# Old_Shutters_Signal_Interface.net
KiCad netlist of a schematic drawn in EAGLE
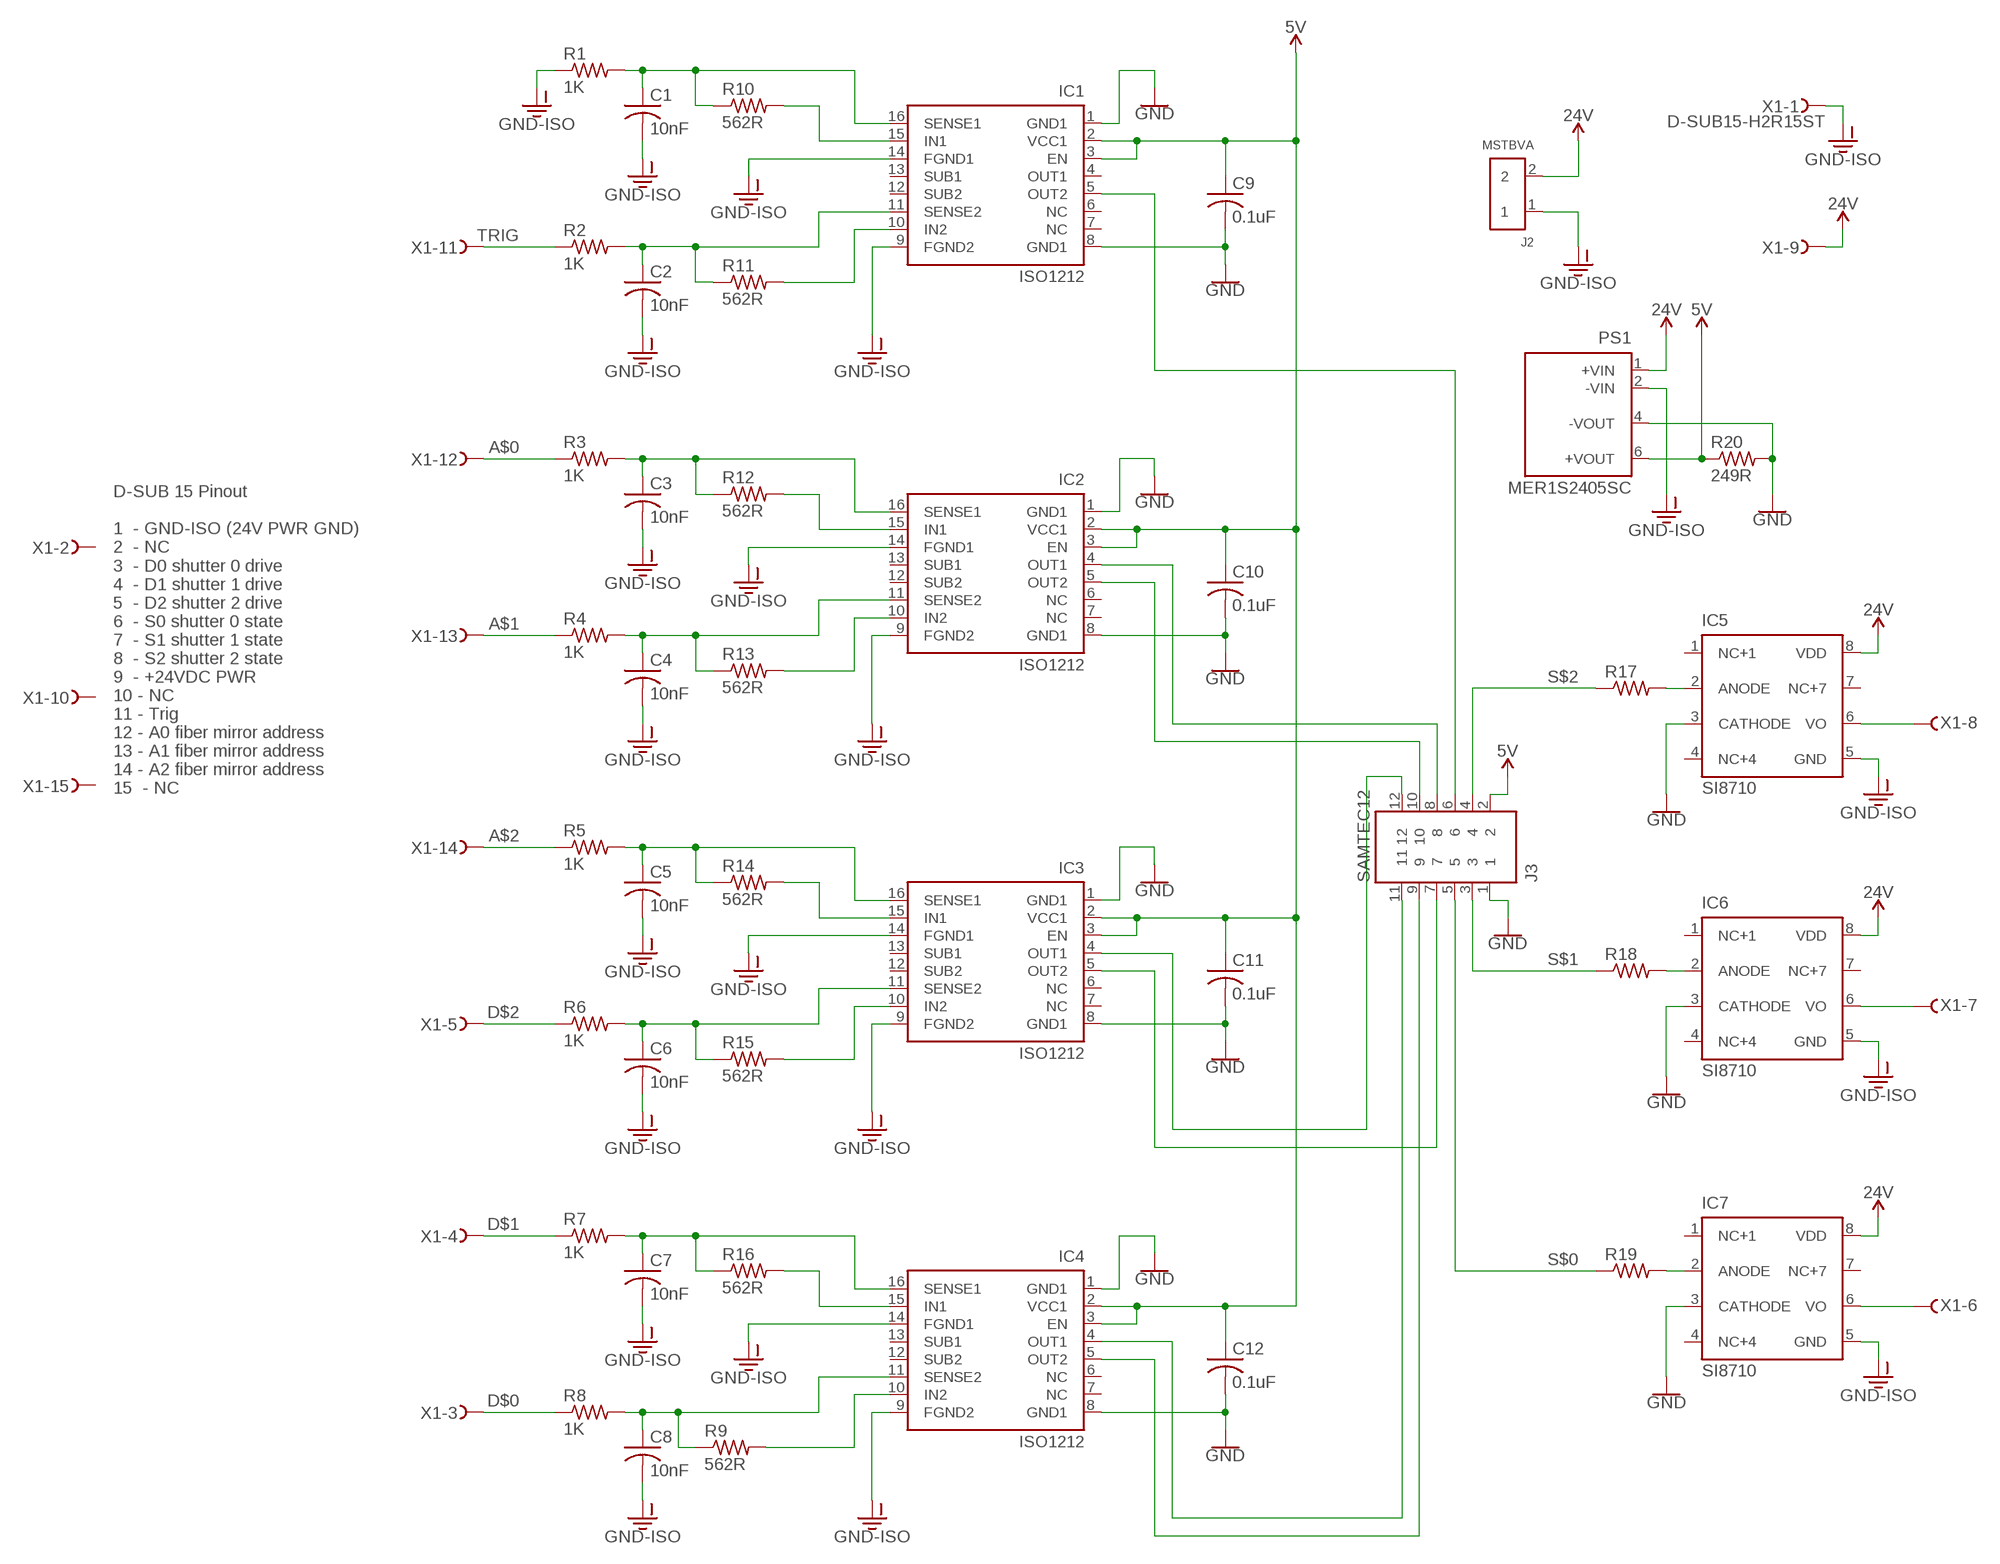
[diagram p0: schematic, sheet 1]

(export (version "E")
  (design (tool "Eeschema 10.0.6"))
  (components
    (comp (ref "C1")
      (value "10nF")
      (footprint "eagle-import:C0805")
      (libsource (lib "eagle-import") (part "C-USC0805"))
    )
    (comp (ref "C2")
      (value "10nF")
      (footprint "eagle-import:C0805")
      (libsource (lib "eagle-import") (part "C-USC0805"))
    )
    (comp (ref "C3")
      (value "10nF")
      (footprint "eagle-import:C0805")
      (libsource (lib "eagle-import") (part "C-USC0805"))
    )
    (comp (ref "C4")
      (value "10nF")
      (footprint "eagle-import:C0805")
      (libsource (lib "eagle-import") (part "C-USC0805"))
    )
    (comp (ref "C5")
      (value "10nF")
      (footprint "eagle-import:C0805")
      (libsource (lib "eagle-import") (part "C-USC0805"))
    )
    (comp (ref "C6")
      (value "10nF")
      (footprint "eagle-import:C0805")
      (libsource (lib "eagle-import") (part "C-USC0805"))
    )
    (comp (ref "C7")
      (value "10nF")
      (footprint "eagle-import:C0805")
      (libsource (lib "eagle-import") (part "C-USC0805"))
    )
    (comp (ref "C8")
      (value "10nF")
      (footprint "eagle-import:C0805")
      (libsource (lib "eagle-import") (part "C-USC0805"))
    )
    (comp (ref "C9")
      (value "0.1uF")
      (footprint "eagle-import:C0805")
      (libsource (lib "eagle-import") (part "C-USC0805"))
    )
    (comp (ref "C10")
      (value "0.1uF")
      (footprint "eagle-import:C0805")
      (libsource (lib "eagle-import") (part "C-USC0805"))
    )
    (comp (ref "C11")
      (value "0.1uF")
      (footprint "eagle-import:C0805")
      (libsource (lib "eagle-import") (part "C-USC0805"))
    )
    (comp (ref "C12")
      (value "0.1uF")
      (footprint "eagle-import:C0805")
      (libsource (lib "eagle-import") (part "C-USC0805"))
    )
    (comp (ref "IC1")
      (value "ISO1212")
      (footprint "eagle-import:ISO1212")
      (libsource (lib "eagle-import") (part "ISO1212"))
    )
    (comp (ref "IC2")
      (value "ISO1212")
      (footprint "eagle-import:ISO1212")
      (libsource (lib "eagle-import") (part "ISO1212"))
    )
    (comp (ref "IC3")
      (value "ISO1212")
      (footprint "eagle-import:ISO1212")
      (libsource (lib "eagle-import") (part "ISO1212"))
    )
    (comp (ref "IC4")
      (value "ISO1212")
      (footprint "eagle-import:ISO1212")
      (libsource (lib "eagle-import") (part "ISO1212"))
    )
    (comp (ref "IC5")
      (value "SI8710")
      (footprint "eagle-import:SO08")
      (libsource (lib "eagle-import") (part "SI8710"))
    )
    (comp (ref "IC6")
      (value "SI8710")
      (footprint "eagle-import:SO08")
      (libsource (lib "eagle-import") (part "SI8710"))
    )
    (comp (ref "IC7")
      (value "SI8710")
      (footprint "eagle-import:SO08")
      (libsource (lib "eagle-import") (part "SI8710"))
    )
    (comp (ref "J2")
      (value "MSTBVA")
      (footprint "eagle-import:MSTBVA")
      (libsource (lib "eagle-import") (part "MSTBVA"))
    )
    (comp (ref "J3")
      (value "SAMTEC12")
      (footprint "eagle-import:SAMTEC12")
      (libsource (lib "eagle-import") (part "SAMTEC12"))
    )
    (comp (ref "PS1")
      (value "MER1S2405SC")
      (footprint "eagle-import:MER1")
      (libsource (lib "eagle-import") (part "MER1"))
    )
    (comp (ref "R1")
      (value "1K")
      (footprint "eagle-import:R0805")
      (libsource (lib "eagle-import") (part "R-US_R0805"))
    )
    (comp (ref "R2")
      (value "1K")
      (footprint "eagle-import:R0805")
      (libsource (lib "eagle-import") (part "R-US_R0805"))
    )
    (comp (ref "R3")
      (value "1K")
      (footprint "eagle-import:R0805")
      (libsource (lib "eagle-import") (part "R-US_R0805"))
    )
    (comp (ref "R4")
      (value "1K")
      (footprint "eagle-import:R0805")
      (libsource (lib "eagle-import") (part "R-US_R0805"))
    )
    (comp (ref "R5")
      (value "1K")
      (footprint "eagle-import:R0805")
      (libsource (lib "eagle-import") (part "R-US_R0805"))
    )
    (comp (ref "R6")
      (value "1K")
      (footprint "eagle-import:R0805")
      (libsource (lib "eagle-import") (part "R-US_R0805"))
    )
    (comp (ref "R7")
      (value "1K")
      (footprint "eagle-import:R0805")
      (libsource (lib "eagle-import") (part "R-US_R0805"))
    )
    (comp (ref "R8")
      (value "1K")
      (footprint "eagle-import:R0805")
      (libsource (lib "eagle-import") (part "R-US_R0805"))
    )
    (comp (ref "R9")
      (value "562R")
      (footprint "eagle-import:R0805")
      (libsource (lib "eagle-import") (part "R-US_R0805"))
    )
    (comp (ref "R10")
      (value "562R")
      (footprint "eagle-import:R0805")
      (libsource (lib "eagle-import") (part "R-US_R0805"))
    )
    (comp (ref "R11")
      (value "562R")
      (footprint "eagle-import:R0805")
      (libsource (lib "eagle-import") (part "R-US_R0805"))
    )
    (comp (ref "R12")
      (value "562R")
      (footprint "eagle-import:R0805")
      (libsource (lib "eagle-import") (part "R-US_R0805"))
    )
    (comp (ref "R13")
      (value "562R")
      (footprint "eagle-import:R0805")
      (libsource (lib "eagle-import") (part "R-US_R0805"))
    )
    (comp (ref "R14")
      (value "562R")
      (footprint "eagle-import:R0805")
      (libsource (lib "eagle-import") (part "R-US_R0805"))
    )
    (comp (ref "R15")
      (value "562R")
      (footprint "eagle-import:R0805")
      (libsource (lib "eagle-import") (part "R-US_R0805"))
    )
    (comp (ref "R16")
      (value "562R")
      (footprint "eagle-import:R0805")
      (libsource (lib "eagle-import") (part "R-US_R0805"))
    )
    (comp (ref "R17")
      (value "R-US_R0805")
      (footprint "eagle-import:R0805")
      (libsource (lib "eagle-import") (part "R-US_R0805"))
    )
    (comp (ref "R18")
      (value "R-US_R0805")
      (footprint "eagle-import:R0805")
      (libsource (lib "eagle-import") (part "R-US_R0805"))
    )
    (comp (ref "R19")
      (value "R-US_R0805")
      (footprint "eagle-import:R0805")
      (libsource (lib "eagle-import") (part "R-US_R0805"))
    )
    (comp (ref "R20")
      (value "249R")
      (footprint "eagle-import:R0805")
      (libsource (lib "eagle-import") (part "R-US_R0805"))
    )
    (comp (ref "X1")
      (value "D-SUB15-H2R15ST")
      (footprint "eagle-import:H2R15ST")
      (libsource (lib "eagle-import") (part "D-SUB15-H2R15ST"))
    )
  )
  (nets
    (net (code "1") (name "/A$0") (class "Default")
      (node (ref "R3") (pin "1") (pinfunction "1_1") (pintype "passive"))
      (node (ref "X1") (pin "12") (pinfunction "F_12") (pintype "passive"))
    )
    (net (code "2") (name "/A$1") (class "Default")
      (node (ref "R4") (pin "1") (pinfunction "1_1") (pintype "passive"))
      (node (ref "X1") (pin "13") (pinfunction "F_13") (pintype "passive"))
    )
    (net (code "3") (name "/A$2") (class "Default")
      (node (ref "R5") (pin "1") (pinfunction "1_1") (pintype "passive"))
      (node (ref "X1") (pin "14") (pinfunction "F_14") (pintype "passive"))
    )
    (net (code "4") (name "/D$0") (class "Default")
      (node (ref "R8") (pin "1") (pinfunction "1_1") (pintype "passive"))
      (node (ref "X1") (pin "3") (pinfunction "F_3") (pintype "passive"))
    )
    (net (code "5") (name "/D$1") (class "Default")
      (node (ref "R7") (pin "1") (pinfunction "1_1") (pintype "passive"))
      (node (ref "X1") (pin "4") (pinfunction "F_4") (pintype "passive"))
    )
    (net (code "6") (name "/D$2") (class "Default")
      (node (ref "R6") (pin "1") (pinfunction "1_1") (pintype "passive"))
      (node (ref "X1") (pin "5") (pinfunction "F_5") (pintype "passive"))
    )
    (net (code "7") (name "/S$0") (class "Default")
      (node (ref "J3") (pin "5") (pinfunction "5_5") (pintype "bidirectional"))
      (node (ref "R19") (pin "1") (pinfunction "1_1") (pintype "passive"))
    )
    (net (code "8") (name "/S$1") (class "Default")
      (node (ref "J3") (pin "3") (pinfunction "3_3") (pintype "bidirectional"))
      (node (ref "R18") (pin "1") (pinfunction "1_1") (pintype "passive"))
    )
    (net (code "9") (name "/S$2") (class "Default")
      (node (ref "J3") (pin "4") (pinfunction "4_4") (pintype "bidirectional"))
      (node (ref "R17") (pin "1") (pinfunction "1_1") (pintype "passive"))
    )
    (net (code "10") (name "/TRIG") (class "Default")
      (node (ref "R2") (pin "1") (pinfunction "1_1") (pintype "passive"))
      (node (ref "X1") (pin "11") (pinfunction "F_11") (pintype "passive"))
    )
    (net (code "11") (name "5V") (class "Default")
      (node (ref "C10") (pin "1") (pinfunction "1_1") (pintype "passive"))
      (node (ref "C11") (pin "1") (pinfunction "1_1") (pintype "passive"))
      (node (ref "C12") (pin "1") (pinfunction "1_1") (pintype "passive"))
      (node (ref "C9") (pin "1") (pinfunction "1_1") (pintype "passive"))
      (node (ref "IC1") (pin "2") (pinfunction "VCC1_2") (pintype "power_in"))
      (node (ref "IC1") (pin "3") (pinfunction "EN_3") (pintype "input"))
      (node (ref "IC2") (pin "2") (pinfunction "VCC1_2") (pintype "power_in"))
      (node (ref "IC2") (pin "3") (pinfunction "EN_3") (pintype "input"))
      (node (ref "IC3") (pin "2") (pinfunction "VCC1_2") (pintype "power_in"))
      (node (ref "IC3") (pin "3") (pinfunction "EN_3") (pintype "input"))
      (node (ref "IC4") (pin "2") (pinfunction "VCC1_2") (pintype "power_in"))
      (node (ref "IC4") (pin "3") (pinfunction "EN_3") (pintype "input"))
      (node (ref "J3") (pin "2") (pinfunction "2_2") (pintype "bidirectional"))
      (node (ref "PS1") (pin "6") (pinfunction "+VOUT_6") (pintype "power_in"))
      (node (ref "R20") (pin "1") (pinfunction "1_1") (pintype "passive"))
    )
    (net (code "12") (name "24V") (class "Default")
      (node (ref "IC5") (pin "8") (pinfunction "VDD_8") (pintype "power_in"))
      (node (ref "IC6") (pin "8") (pinfunction "VDD_8") (pintype "power_in"))
      (node (ref "IC7") (pin "8") (pinfunction "VDD_8") (pintype "power_in"))
      (node (ref "J2") (pin "2") (pinfunction "2_2") (pintype "power_in"))
      (node (ref "PS1") (pin "1") (pinfunction "+VIN_1") (pintype "power_in"))
      (node (ref "X1") (pin "9") (pinfunction "F_9") (pintype "passive"))
    )
    (net (code "13") (name "GND") (class "Default")
      (node (ref "C10") (pin "2") (pinfunction "2_2") (pintype "passive"))
      (node (ref "C11") (pin "2") (pinfunction "2_2") (pintype "passive"))
      (node (ref "C12") (pin "2") (pinfunction "2_2") (pintype "passive"))
      (node (ref "C9") (pin "2") (pinfunction "2_2") (pintype "passive"))
      (node (ref "IC1") (pin "1") (pinfunction "GND1_1") (pintype "power_in"))
      (node (ref "IC1") (pin "8") (pinfunction "GND1_8") (pintype "power_in"))
      (node (ref "IC2") (pin "1") (pinfunction "GND1_1") (pintype "power_in"))
      (node (ref "IC2") (pin "8") (pinfunction "GND1_8") (pintype "power_in"))
      (node (ref "IC3") (pin "1") (pinfunction "GND1_1") (pintype "power_in"))
      (node (ref "IC3") (pin "8") (pinfunction "GND1_8") (pintype "power_in"))
      (node (ref "IC4") (pin "1") (pinfunction "GND1_1") (pintype "power_in"))
      (node (ref "IC4") (pin "8") (pinfunction "GND1_8") (pintype "power_in"))
      (node (ref "IC5") (pin "3") (pinfunction "CATHODE_3") (pintype "power_in"))
      (node (ref "IC6") (pin "3") (pinfunction "CATHODE_3") (pintype "power_in"))
      (node (ref "IC7") (pin "3") (pinfunction "CATHODE_3") (pintype "power_in"))
      (node (ref "J3") (pin "1") (pinfunction "1_1") (pintype "bidirectional"))
      (node (ref "PS1") (pin "4") (pinfunction "-VOUT_4") (pintype "power_in"))
      (node (ref "R20") (pin "2") (pinfunction "2_2") (pintype "passive"))
    )
    (net (code "14") (name "GND-ISO") (class "Default")
      (node (ref "C1") (pin "2") (pinfunction "2_2") (pintype "passive"))
      (node (ref "C2") (pin "2") (pinfunction "2_2") (pintype "passive"))
      (node (ref "C3") (pin "2") (pinfunction "2_2") (pintype "passive"))
      (node (ref "C4") (pin "2") (pinfunction "2_2") (pintype "passive"))
      (node (ref "C5") (pin "2") (pinfunction "2_2") (pintype "passive"))
      (node (ref "C6") (pin "2") (pinfunction "2_2") (pintype "passive"))
      (node (ref "C7") (pin "2") (pinfunction "2_2") (pintype "passive"))
      (node (ref "C8") (pin "2") (pinfunction "2_2") (pintype "passive"))
      (node (ref "IC1") (pin "14") (pinfunction "FGND1_14") (pintype "bidirectional"))
      (node (ref "IC1") (pin "9") (pinfunction "FGND2_9") (pintype "power_in"))
      (node (ref "IC2") (pin "14") (pinfunction "FGND1_14") (pintype "bidirectional"))
      (node (ref "IC2") (pin "9") (pinfunction "FGND2_9") (pintype "power_in"))
      (node (ref "IC3") (pin "14") (pinfunction "FGND1_14") (pintype "bidirectional"))
      (node (ref "IC3") (pin "9") (pinfunction "FGND2_9") (pintype "power_in"))
      (node (ref "IC4") (pin "14") (pinfunction "FGND1_14") (pintype "bidirectional"))
      (node (ref "IC4") (pin "9") (pinfunction "FGND2_9") (pintype "power_in"))
      (node (ref "IC5") (pin "5") (pinfunction "GND_5") (pintype "power_in"))
      (node (ref "IC6") (pin "5") (pinfunction "GND_5") (pintype "power_in"))
      (node (ref "IC7") (pin "5") (pinfunction "GND_5") (pintype "power_in"))
      (node (ref "J2") (pin "1") (pinfunction "1_1") (pintype "power_in"))
      (node (ref "PS1") (pin "2") (pinfunction "-VIN_2") (pintype "power_in"))
      (node (ref "R1") (pin "1") (pinfunction "1_1") (pintype "passive"))
      (node (ref "X1") (pin "1") (pinfunction "F_1") (pintype "passive"))
    )
    (net (code "15") (name "Net-(IC1-IN1)") (class "Default")
      (node (ref "IC1") (pin "15") (pinfunction "IN1_15") (pintype "input"))
      (node (ref "R10") (pin "2") (pinfunction "2_2") (pintype "passive"))
    )
    (net (code "16") (name "Net-(IC1-IN2)") (class "Default")
      (node (ref "IC1") (pin "10") (pinfunction "IN2_10") (pintype "input"))
      (node (ref "R11") (pin "2") (pinfunction "2_2") (pintype "passive"))
    )
    (net (code "17") (name "Net-(IC1-OUT2)") (class "Default")
      (node (ref "IC1") (pin "5") (pinfunction "OUT2_5") (pintype "output"))
      (node (ref "J3") (pin "6") (pinfunction "6_6") (pintype "bidirectional"))
    )
    (net (code "18") (name "Net-(IC1-SENSE1)") (class "Default")
      (node (ref "C1") (pin "1") (pinfunction "1_1") (pintype "passive"))
      (node (ref "IC1") (pin "16") (pinfunction "SENSE1_16") (pintype "input"))
      (node (ref "R1") (pin "2") (pinfunction "2_2") (pintype "passive"))
      (node (ref "R10") (pin "1") (pinfunction "1_1") (pintype "passive"))
    )
    (net (code "19") (name "Net-(IC1-SENSE2)") (class "Default")
      (node (ref "C2") (pin "1") (pinfunction "1_1") (pintype "passive"))
      (node (ref "IC1") (pin "11") (pinfunction "SENSE2_11") (pintype "input"))
      (node (ref "R11") (pin "1") (pinfunction "1_1") (pintype "passive"))
      (node (ref "R2") (pin "2") (pinfunction "2_2") (pintype "passive"))
    )
    (net (code "20") (name "Net-(IC2-IN1)") (class "Default")
      (node (ref "IC2") (pin "15") (pinfunction "IN1_15") (pintype "input"))
      (node (ref "R12") (pin "2") (pinfunction "2_2") (pintype "passive"))
    )
    (net (code "21") (name "Net-(IC2-IN2)") (class "Default")
      (node (ref "IC2") (pin "10") (pinfunction "IN2_10") (pintype "input"))
      (node (ref "R13") (pin "2") (pinfunction "2_2") (pintype "passive"))
    )
    (net (code "22") (name "Net-(IC2-OUT1)") (class "Default")
      (node (ref "IC2") (pin "4") (pinfunction "OUT1_4") (pintype "output"))
      (node (ref "J3") (pin "8") (pinfunction "8_8") (pintype "bidirectional"))
    )
    (net (code "23") (name "Net-(IC2-OUT2)") (class "Default")
      (node (ref "IC2") (pin "5") (pinfunction "OUT2_5") (pintype "output"))
      (node (ref "J3") (pin "10") (pinfunction "10_10") (pintype "bidirectional"))
    )
    (net (code "24") (name "Net-(IC2-SENSE1)") (class "Default")
      (node (ref "C3") (pin "1") (pinfunction "1_1") (pintype "passive"))
      (node (ref "IC2") (pin "16") (pinfunction "SENSE1_16") (pintype "input"))
      (node (ref "R12") (pin "1") (pinfunction "1_1") (pintype "passive"))
      (node (ref "R3") (pin "2") (pinfunction "2_2") (pintype "passive"))
    )
    (net (code "25") (name "Net-(IC2-SENSE2)") (class "Default")
      (node (ref "C4") (pin "1") (pinfunction "1_1") (pintype "passive"))
      (node (ref "IC2") (pin "11") (pinfunction "SENSE2_11") (pintype "input"))
      (node (ref "R13") (pin "1") (pinfunction "1_1") (pintype "passive"))
      (node (ref "R4") (pin "2") (pinfunction "2_2") (pintype "passive"))
    )
    (net (code "26") (name "Net-(IC3-IN1)") (class "Default")
      (node (ref "IC3") (pin "15") (pinfunction "IN1_15") (pintype "input"))
      (node (ref "R14") (pin "2") (pinfunction "2_2") (pintype "passive"))
    )
    (net (code "27") (name "Net-(IC3-IN2)") (class "Default")
      (node (ref "IC3") (pin "10") (pinfunction "IN2_10") (pintype "input"))
      (node (ref "R15") (pin "2") (pinfunction "2_2") (pintype "passive"))
    )
    (net (code "28") (name "Net-(IC3-OUT1)") (class "Default")
      (node (ref "IC3") (pin "4") (pinfunction "OUT1_4") (pintype "output"))
      (node (ref "J3") (pin "12") (pinfunction "12_12") (pintype "bidirectional"))
    )
    (net (code "29") (name "Net-(IC3-OUT2)") (class "Default")
      (node (ref "IC3") (pin "5") (pinfunction "OUT2_5") (pintype "output"))
      (node (ref "J3") (pin "7") (pinfunction "7_7") (pintype "bidirectional"))
    )
    (net (code "30") (name "Net-(IC3-SENSE1)") (class "Default")
      (node (ref "C5") (pin "1") (pinfunction "1_1") (pintype "passive"))
      (node (ref "IC3") (pin "16") (pinfunction "SENSE1_16") (pintype "input"))
      (node (ref "R14") (pin "1") (pinfunction "1_1") (pintype "passive"))
      (node (ref "R5") (pin "2") (pinfunction "2_2") (pintype "passive"))
    )
    (net (code "31") (name "Net-(IC3-SENSE2)") (class "Default")
      (node (ref "C6") (pin "1") (pinfunction "1_1") (pintype "passive"))
      (node (ref "IC3") (pin "11") (pinfunction "SENSE2_11") (pintype "input"))
      (node (ref "R15") (pin "1") (pinfunction "1_1") (pintype "passive"))
      (node (ref "R6") (pin "2") (pinfunction "2_2") (pintype "passive"))
    )
    (net (code "32") (name "Net-(IC4-IN1)") (class "Default")
      (node (ref "IC4") (pin "15") (pinfunction "IN1_15") (pintype "input"))
      (node (ref "R16") (pin "2") (pinfunction "2_2") (pintype "passive"))
    )
    (net (code "33") (name "Net-(IC4-IN2)") (class "Default")
      (node (ref "IC4") (pin "10") (pinfunction "IN2_10") (pintype "input"))
      (node (ref "R9") (pin "2") (pinfunction "2_2") (pintype "passive"))
    )
    (net (code "34") (name "Net-(IC4-OUT1)") (class "Default")
      (node (ref "IC4") (pin "4") (pinfunction "OUT1_4") (pintype "output"))
      (node (ref "J3") (pin "11") (pinfunction "11_11") (pintype "bidirectional"))
    )
    (net (code "35") (name "Net-(IC4-OUT2)") (class "Default")
      (node (ref "IC4") (pin "5") (pinfunction "OUT2_5") (pintype "output"))
      (node (ref "J3") (pin "9") (pinfunction "9_9") (pintype "bidirectional"))
    )
    (net (code "36") (name "Net-(IC4-SENSE1)") (class "Default")
      (node (ref "C7") (pin "1") (pinfunction "1_1") (pintype "passive"))
      (node (ref "IC4") (pin "16") (pinfunction "SENSE1_16") (pintype "input"))
      (node (ref "R16") (pin "1") (pinfunction "1_1") (pintype "passive"))
      (node (ref "R7") (pin "2") (pinfunction "2_2") (pintype "passive"))
    )
    (net (code "37") (name "Net-(IC4-SENSE2)") (class "Default")
      (node (ref "C8") (pin "1") (pinfunction "1_1") (pintype "passive"))
      (node (ref "IC4") (pin "11") (pinfunction "SENSE2_11") (pintype "input"))
      (node (ref "R8") (pin "2") (pinfunction "2_2") (pintype "passive"))
      (node (ref "R9") (pin "1") (pinfunction "1_1") (pintype "passive"))
    )
    (net (code "38") (name "Net-(IC5-ANODE)") (class "Default")
      (node (ref "IC5") (pin "2") (pinfunction "ANODE_2") (pintype "input"))
      (node (ref "R17") (pin "2") (pinfunction "2_2") (pintype "passive"))
    )
    (net (code "39") (name "Net-(IC5-VO)") (class "Default")
      (node (ref "IC5") (pin "6") (pinfunction "VO_6") (pintype "output"))
      (node (ref "X1") (pin "8") (pinfunction "F_8") (pintype "passive"))
    )
    (net (code "40") (name "Net-(IC6-ANODE)") (class "Default")
      (node (ref "IC6") (pin "2") (pinfunction "ANODE_2") (pintype "input"))
      (node (ref "R18") (pin "2") (pinfunction "2_2") (pintype "passive"))
    )
    (net (code "41") (name "Net-(IC6-VO)") (class "Default")
      (node (ref "IC6") (pin "6") (pinfunction "VO_6") (pintype "output"))
      (node (ref "X1") (pin "7") (pinfunction "F_7") (pintype "passive"))
    )
    (net (code "42") (name "Net-(IC7-ANODE)") (class "Default")
      (node (ref "IC7") (pin "2") (pinfunction "ANODE_2") (pintype "input"))
      (node (ref "R19") (pin "2") (pinfunction "2_2") (pintype "passive"))
    )
    (net (code "43") (name "Net-(IC7-VO)") (class "Default")
      (node (ref "IC7") (pin "6") (pinfunction "VO_6") (pintype "output"))
      (node (ref "X1") (pin "6") (pinfunction "F_6") (pintype "passive"))
    )
    (net (code "44") (name "unconnected-(IC1-NC-Pad6)") (class "Default")
      (node (ref "IC1") (pin "6") (pinfunction "NC_6") (pintype "no_connect"))
    )
    (net (code "45") (name "unconnected-(IC1-NC-Pad7)") (class "Default")
      (node (ref "IC1") (pin "7") (pinfunction "NC_7") (pintype "no_connect"))
    )
    (net (code "46") (name "unconnected-(IC1-OUT1-Pad4)") (class "Default")
      (node (ref "IC1") (pin "4") (pinfunction "OUT1_4") (pintype "output"))
    )
    (net (code "47") (name "unconnected-(IC1-SUB1-Pad13)") (class "Default")
      (node (ref "IC1") (pin "13") (pinfunction "SUB1_13") (pintype "no_connect"))
    )
    (net (code "48") (name "unconnected-(IC1-SUB2-Pad12)") (class "Default")
      (node (ref "IC1") (pin "12") (pinfunction "SUB2_12") (pintype "no_connect"))
    )
    (net (code "49") (name "unconnected-(IC2-NC-Pad6)") (class "Default")
      (node (ref "IC2") (pin "6") (pinfunction "NC_6") (pintype "no_connect"))
    )
    (net (code "50") (name "unconnected-(IC2-NC-Pad7)") (class "Default")
      (node (ref "IC2") (pin "7") (pinfunction "NC_7") (pintype "no_connect"))
    )
    (net (code "51") (name "unconnected-(IC2-SUB1-Pad13)") (class "Default")
      (node (ref "IC2") (pin "13") (pinfunction "SUB1_13") (pintype "no_connect"))
    )
    (net (code "52") (name "unconnected-(IC2-SUB2-Pad12)") (class "Default")
      (node (ref "IC2") (pin "12") (pinfunction "SUB2_12") (pintype "no_connect"))
    )
    (net (code "53") (name "unconnected-(IC3-NC-Pad6)") (class "Default")
      (node (ref "IC3") (pin "6") (pinfunction "NC_6") (pintype "no_connect"))
    )
    (net (code "54") (name "unconnected-(IC3-NC-Pad7)") (class "Default")
      (node (ref "IC3") (pin "7") (pinfunction "NC_7") (pintype "no_connect"))
    )
    (net (code "55") (name "unconnected-(IC3-SUB1-Pad13)") (class "Default")
      (node (ref "IC3") (pin "13") (pinfunction "SUB1_13") (pintype "no_connect"))
    )
    (net (code "56") (name "unconnected-(IC3-SUB2-Pad12)") (class "Default")
      (node (ref "IC3") (pin "12") (pinfunction "SUB2_12") (pintype "no_connect"))
    )
    (net (code "57") (name "unconnected-(IC4-NC-Pad6)") (class "Default")
      (node (ref "IC4") (pin "6") (pinfunction "NC_6") (pintype "no_connect"))
    )
    (net (code "58") (name "unconnected-(IC4-NC-Pad7)") (class "Default")
      (node (ref "IC4") (pin "7") (pinfunction "NC_7") (pintype "no_connect"))
    )
    (net (code "59") (name "unconnected-(IC4-SUB1-Pad13)") (class "Default")
      (node (ref "IC4") (pin "13") (pinfunction "SUB1_13") (pintype "no_connect"))
    )
    (net (code "60") (name "unconnected-(IC4-SUB2-Pad12)") (class "Default")
      (node (ref "IC4") (pin "12") (pinfunction "SUB2_12") (pintype "no_connect"))
    )
    (net (code "61") (name "unconnected-(IC5-NC+1-Pad1)") (class "Default")
      (node (ref "IC5") (pin "1") (pinfunction "NC+1_1") (pintype "no_connect"))
    )
    (net (code "62") (name "unconnected-(IC5-NC+4-Pad4)") (class "Default")
      (node (ref "IC5") (pin "4") (pinfunction "NC+4_4") (pintype "no_connect"))
    )
    (net (code "63") (name "unconnected-(IC5-NC+7-Pad7)") (class "Default")
      (node (ref "IC5") (pin "7") (pinfunction "NC+7_7") (pintype "output"))
    )
    (net (code "64") (name "unconnected-(IC6-NC+1-Pad1)") (class "Default")
      (node (ref "IC6") (pin "1") (pinfunction "NC+1_1") (pintype "no_connect"))
    )
    (net (code "65") (name "unconnected-(IC6-NC+4-Pad4)") (class "Default")
      (node (ref "IC6") (pin "4") (pinfunction "NC+4_4") (pintype "no_connect"))
    )
    (net (code "66") (name "unconnected-(IC6-NC+7-Pad7)") (class "Default")
      (node (ref "IC6") (pin "7") (pinfunction "NC+7_7") (pintype "output"))
    )
    (net (code "67") (name "unconnected-(IC7-NC+1-Pad1)") (class "Default")
      (node (ref "IC7") (pin "1") (pinfunction "NC+1_1") (pintype "no_connect"))
    )
    (net (code "68") (name "unconnected-(IC7-NC+4-Pad4)") (class "Default")
      (node (ref "IC7") (pin "4") (pinfunction "NC+4_4") (pintype "no_connect"))
    )
    (net (code "69") (name "unconnected-(IC7-NC+7-Pad7)") (class "Default")
      (node (ref "IC7") (pin "7") (pinfunction "NC+7_7") (pintype "output"))
    )
    (net (code "70") (name "unconnected-(X1B-F-Pad10)") (class "Default")
      (node (ref "X1") (pin "10") (pinfunction "F_10") (pintype "passive"))
    )
    (net (code "71") (name "unconnected-(X1G-F-Pad15)") (class "Default")
      (node (ref "X1") (pin "15") (pinfunction "F_15") (pintype "passive"))
    )
    (net (code "72") (name "unconnected-(X1H-F-Pad2)") (class "Default")
      (node (ref "X1") (pin "2") (pinfunction "F_2") (pintype "passive"))
    )
  )
)
